# xlr_blinker_board.net
KiCad netlist of a schematic drawn in EAGLE
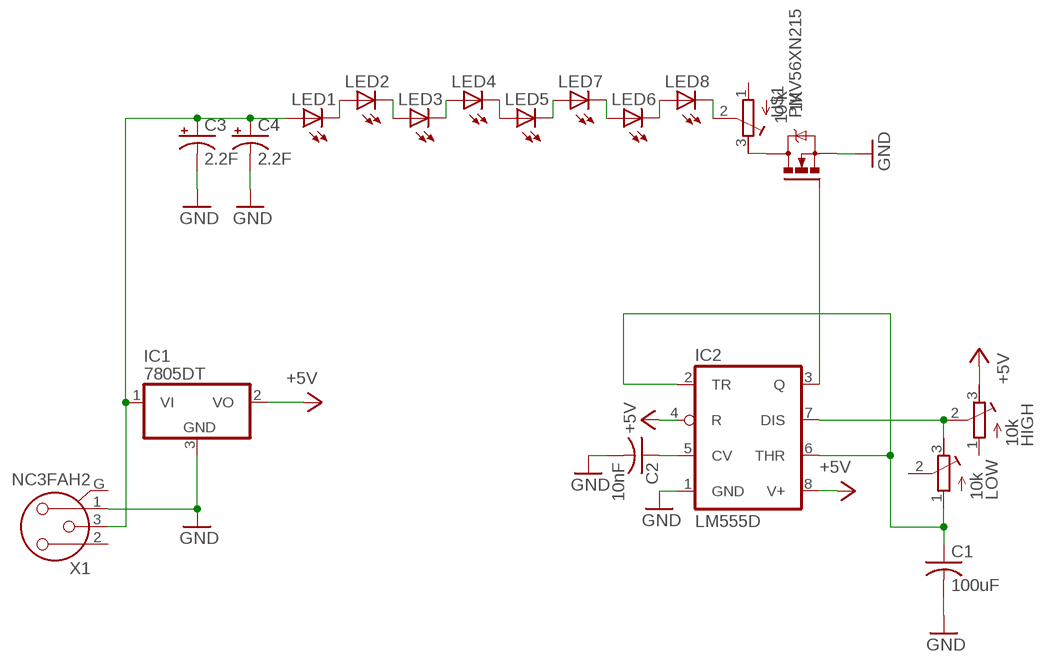
[diagram p0: schematic, sheet 1]

(export (version "E")
  (design (tool "Eeschema 10.0.6"))
  (components
    (comp (ref "1K")
      (value "10 k")
      (footprint "eagle-import:RTRIM3314J")
      (libsource (lib "eagle-import") (part "R-TRIMM3314J"))
    )
    (comp (ref "C1")
      (value "100uF")
      (footprint "eagle-import:C1206")
      (libsource (lib "eagle-import") (part "C-USC1206"))
    )
    (comp (ref "C2")
      (value "10nF")
      (footprint "eagle-import:C1206")
      (libsource (lib "eagle-import") (part "C-USC1206"))
    )
    (comp (ref "C3")
      (value "2.2F")
      (footprint "eagle-import:E5-10,5")
      (libsource (lib "eagle-import") (part "CPOL-USE5-10.5"))
    )
    (comp (ref "C4")
      (value "2.2F")
      (footprint "eagle-import:E5-10,5")
      (libsource (lib "eagle-import") (part "CPOL-USE5-10.5"))
    )
    (comp (ref "HIGH")
      (value "10k")
      (footprint "eagle-import:RTRIM3314J")
      (libsource (lib "eagle-import") (part "R-TRIMM3314J"))
    )
    (comp (ref "IC1")
      (value "7805DT")
      (footprint "eagle-import:TO252")
      (libsource (lib "eagle-import") (part "78DT05"))
    )
    (comp (ref "IC2")
      (value "LM555D")
      (footprint "eagle-import:SO08")
      (libsource (lib "eagle-import") (part "555DLM"))
    )
    (comp (ref "LED1")
      (value "LEDCHIPLED_1206")
      (footprint "eagle-import:CHIPLED_1206")
      (libsource (lib "eagle-import") (part "LEDCHIPLED_1206"))
    )
    (comp (ref "LED2")
      (value "LEDCHIPLED_1206")
      (footprint "eagle-import:CHIPLED_1206")
      (libsource (lib "eagle-import") (part "LEDCHIPLED_1206"))
    )
    (comp (ref "LED3")
      (value "LEDCHIPLED_1206")
      (footprint "eagle-import:CHIPLED_1206")
      (libsource (lib "eagle-import") (part "LEDCHIPLED_1206"))
    )
    (comp (ref "LED4")
      (value "LEDCHIPLED_1206")
      (footprint "eagle-import:CHIPLED_1206")
      (libsource (lib "eagle-import") (part "LEDCHIPLED_1206"))
    )
    (comp (ref "LED5")
      (value "LEDCHIPLED_1206")
      (footprint "eagle-import:CHIPLED_1206")
      (libsource (lib "eagle-import") (part "LEDCHIPLED_1206"))
    )
    (comp (ref "LED6")
      (value "LEDCHIPLED_1206")
      (footprint "eagle-import:CHIPLED_1206")
      (libsource (lib "eagle-import") (part "LEDCHIPLED_1206"))
    )
    (comp (ref "LED7")
      (value "LEDCHIPLED_1206")
      (footprint "eagle-import:CHIPLED_1206")
      (libsource (lib "eagle-import") (part "LEDCHIPLED_1206"))
    )
    (comp (ref "LED8")
      (value "LEDCHIPLED_1206")
      (footprint "eagle-import:CHIPLED_1206")
      (libsource (lib "eagle-import") (part "LEDCHIPLED_1206"))
    )
    (comp (ref "LOW")
      (value "10k")
      (footprint "eagle-import:RTRIM3314J")
      (libsource (lib "eagle-import") (part "R-TRIMM3314J"))
    )
    (comp (ref "U$1")
      (value "PMV56XN215")
      (footprint "eagle-import:SOT23")
      (fields (field (name "PART_NUM") "PMV56XN,215") (field (name "PART_NUM_1") "PMV56XN,215"))
      (libsource (lib "eagle-import") (part "N-CHANNEL_MOSFETPMV56XN,215"))
    )
    (comp (ref "X1")
      (value "NC3FAH2")
      (footprint "eagle-import:NC3FAH2")
      (libsource (lib "eagle-import") (part "NC3FAH2"))
    )
  )
  (nets
    (net (code "1") (name "+5V") (class "Default")
      (node (ref "HIGH") (pin "3") (pinfunction "A_3") (pintype "passive"))
      (node (ref "IC1") (pin "2") (pinfunction "VO_2") (pintype "passive"))
      (node (ref "IC2") (pin "4") (pinfunction "R_4") (pintype "input"))
      (node (ref "IC2") (pin "8") (pinfunction "V+_8") (pintype "power_in"))
    )
    (net (code "2") (name "GND") (class "Default")
      (node (ref "C1") (pin "2") (pinfunction "2_2") (pintype "passive"))
      (node (ref "C2") (pin "2") (pinfunction "2_2") (pintype "passive"))
      (node (ref "C3") (pin "-") (pinfunction "-_-") (pintype "passive"))
      (node (ref "C4") (pin "-") (pinfunction "-_-") (pintype "passive"))
      (node (ref "IC1") (pin "3") (pinfunction "GND_3") (pintype "passive"))
      (node (ref "IC2") (pin "1") (pinfunction "GND_1") (pintype "power_in"))
      (node (ref "U$1") (pin "2") (pinfunction "S_2") (pintype "passive"))
      (node (ref "X1") (pin "1") (pinfunction "2_1") (pintype "passive"))
    )
    (net (code "3") (name "Net-(1K-A)") (class "Default")
      (node (ref "1K") (pin "3") (pinfunction "A_3") (pintype "passive"))
      (node (ref "U$1") (pin "3") (pinfunction "D_3") (pintype "passive"))
    )
    (net (code "4") (name "Net-(1K-S)") (class "Default")
      (node (ref "1K") (pin "2") (pinfunction "S_2") (pintype "passive"))
      (node (ref "LED8") (pin "C") (pinfunction "C_C") (pintype "passive"))
    )
    (net (code "5") (name "Net-(HIGH-S)") (class "Default")
      (node (ref "HIGH") (pin "2") (pinfunction "S_2") (pintype "passive"))
      (node (ref "IC2") (pin "7") (pinfunction "DIS_7") (pintype "input"))
      (node (ref "LOW") (pin "3") (pinfunction "A_3") (pintype "passive"))
    )
    (net (code "6") (name "Net-(IC1-VI)") (class "Default")
      (node (ref "C3") (pin "+") (pinfunction "+_+") (pintype "passive"))
      (node (ref "C4") (pin "+") (pinfunction "+_+") (pintype "passive"))
      (node (ref "IC1") (pin "1") (pinfunction "VI_1") (pintype "input"))
      (node (ref "LED1") (pin "A") (pinfunction "A_A") (pintype "passive"))
      (node (ref "X1") (pin "3") (pinfunction "3_3") (pintype "passive"))
    )
    (net (code "7") (name "Net-(IC2-CV)") (class "Default")
      (node (ref "C2") (pin "1") (pinfunction "1_1") (pintype "passive"))
      (node (ref "IC2") (pin "5") (pinfunction "CV_5") (pintype "input"))
    )
    (net (code "8") (name "Net-(IC2-Q)") (class "Default")
      (node (ref "IC2") (pin "3") (pinfunction "Q_3") (pintype "output"))
      (node (ref "U$1") (pin "1") (pinfunction "G_1") (pintype "passive"))
    )
    (net (code "9") (name "Net-(IC2-THR)") (class "Default")
      (node (ref "C1") (pin "1") (pinfunction "1_1") (pintype "passive"))
      (node (ref "IC2") (pin "2") (pinfunction "TR_2") (pintype "input"))
      (node (ref "IC2") (pin "6") (pinfunction "THR_6") (pintype "input"))
      (node (ref "LOW") (pin "1") (pinfunction "E_1") (pintype "passive"))
    )
    (net (code "10") (name "Net-(LED1-PadC)") (class "Default")
      (node (ref "LED1") (pin "C") (pinfunction "C_C") (pintype "passive"))
      (node (ref "LED2") (pin "A") (pinfunction "A_A") (pintype "passive"))
    )
    (net (code "11") (name "Net-(LED2-PadC)") (class "Default")
      (node (ref "LED2") (pin "C") (pinfunction "C_C") (pintype "passive"))
      (node (ref "LED3") (pin "A") (pinfunction "A_A") (pintype "passive"))
    )
    (net (code "12") (name "Net-(LED3-PadC)") (class "Default")
      (node (ref "LED3") (pin "C") (pinfunction "C_C") (pintype "passive"))
      (node (ref "LED4") (pin "A") (pinfunction "A_A") (pintype "passive"))
    )
    (net (code "13") (name "Net-(LED4-PadC)") (class "Default")
      (node (ref "LED4") (pin "C") (pinfunction "C_C") (pintype "passive"))
      (node (ref "LED5") (pin "A") (pinfunction "A_A") (pintype "passive"))
    )
    (net (code "14") (name "Net-(LED5-PadC)") (class "Default")
      (node (ref "LED5") (pin "C") (pinfunction "C_C") (pintype "passive"))
      (node (ref "LED7") (pin "A") (pinfunction "A_A") (pintype "passive"))
    )
    (net (code "15") (name "Net-(LED6-PadA)") (class "Default")
      (node (ref "LED6") (pin "A") (pinfunction "A_A") (pintype "passive"))
      (node (ref "LED7") (pin "C") (pinfunction "C_C") (pintype "passive"))
    )
    (net (code "16") (name "Net-(LED6-PadC)") (class "Default")
      (node (ref "LED6") (pin "C") (pinfunction "C_C") (pintype "passive"))
      (node (ref "LED8") (pin "A") (pinfunction "A_A") (pintype "passive"))
    )
    (net (code "17") (name "unconnected-(1K-E-Pad1)") (class "Default")
      (node (ref "1K") (pin "1") (pinfunction "E_1") (pintype "passive"))
    )
    (net (code "18") (name "unconnected-(HIGH-E-Pad1)") (class "Default")
      (node (ref "HIGH") (pin "1") (pinfunction "E_1") (pintype "passive"))
    )
    (net (code "19") (name "unconnected-(LOW-S-Pad2)") (class "Default")
      (node (ref "LOW") (pin "2") (pinfunction "S_2") (pintype "passive"))
    )
    (net (code "20") (name "unconnected-(X1-1-Pad2)") (class "Default")
      (node (ref "X1") (pin "2") (pinfunction "1_2") (pintype "passive"))
    )
    (net (code "21") (name "unconnected-(X1-PadG)") (class "Default")
      (node (ref "X1") (pin "G") (pinfunction "G_G") (pintype "passive"))
    )
  )
)
